# QUTMS-BrakeLight-S00.net
KiCad netlist of a schematic drawn in Altium Designer
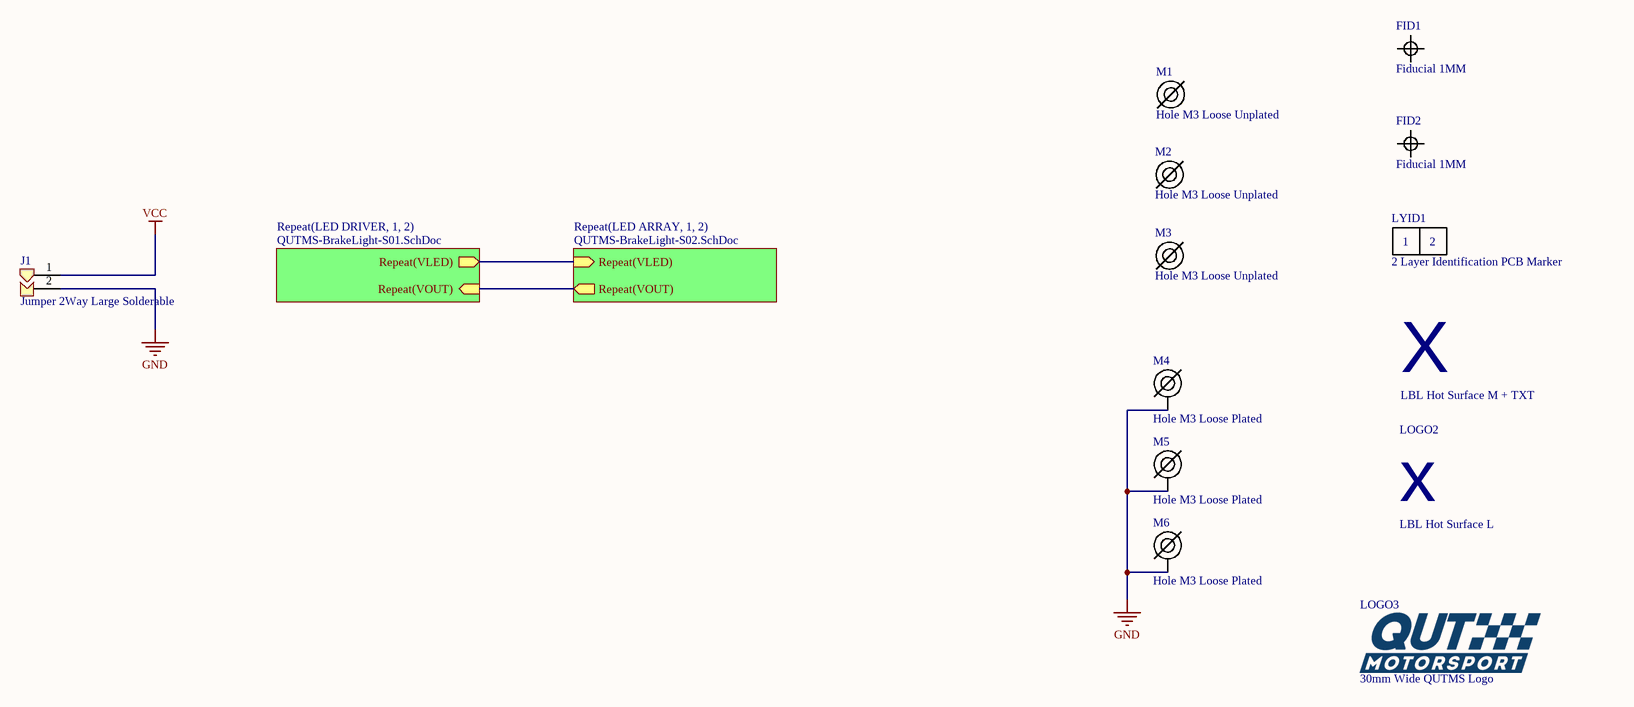
[diagram p0: QUTMS-BrakeLight-S00.SchDoc]

(export (version "E")
  (design (tool "Eeschema 10.0.6"))
  (components
    (comp (ref "FID1")
      (value "Fiducial 1MM")
      (footprint "FIDUCIAL 1MM")
      (libsource (lib "QUTMS_PCBLibrary") (part "Fiducial 1MM"))
    )
    (comp (ref "FID2")
      (value "Fiducial 1MM")
      (footprint "FIDUCIAL 1MM")
      (libsource (lib "QUTMS_PCBLibrary") (part "Fiducial 1MM"))
    )
    (comp (ref "J1")
      (value "Jumper 2Way Large Solderable")
      (footprint "Jumper_2Way_Large_Solder_Pad")
      (description "Jumper 2Way Large Side Solderable Pad")
      (libsource (lib "QUTMS_JumperLibrary") (part "Jumper 2Way Side Large Solder Pad"))
    )
    (comp (ref "LOGO1")
      (value "LBL Hot Surface M + TXT")
      (footprint "LBL HOT MEDIUM TXT")
      (libsource (lib "QUTMS_PCBLibrary") (part "LBL Hot Surface M + TXT"))
    )
    (comp (ref "LOGO2")
      (value "LBL Hot Surface L")
      (footprint "LBL HOT LARGE")
      (libsource (lib "QUTMS_PCBLibrary") (part "LBL Hot Surface L"))
    )
    (comp (ref "LOGO3")
      (value "30mm Wide QUTMS Logo")
      (footprint "QUTMS LOGO 30MM")
      (libsource (lib "QUTMS_PCBLibrary") (part "QUTMS Logo 30mm"))
    )
    (comp (ref "LYID1")
      (value "2 Layer Identification PCB Marker")
      (footprint "LAYER IDENT 2")
      (libsource (lib "QUTMS_PCBLibrary") (part "Layer Identification 2"))
    )
    (comp (ref "M1")
      (value "Hole M3 Loose Unplated")
      (footprint "M3.5 UNPLATED")
      (description "M3.5 Hole, No Plating")
      (libsource (lib "QUTMS_PCBLibrary") (part "Hole M3 Loose Unplated"))
    )
    (comp (ref "M2")
      (value "Hole M3 Loose Unplated")
      (footprint "M3.5 UNPLATED")
      (description "M3.5 Hole, No Plating")
      (libsource (lib "QUTMS_PCBLibrary") (part "Hole M3 Loose Unplated"))
    )
    (comp (ref "M3")
      (value "Hole M3 Loose Unplated")
      (footprint "M3.5 UNPLATED")
      (description "M3.5 Hole, No Plating")
      (libsource (lib "QUTMS_PCBLibrary") (part "Hole M3 Loose Unplated"))
    )
    (comp (ref "M4")
      (value "Hole M3 Loose Plated")
      (footprint "M3.5 PLATED")
      (description "M3.5 Hole, Plated")
      (libsource (lib "QUTMS_PCBLibrary") (part "Hole M3 Loose Plated"))
    )
    (comp (ref "M5")
      (value "Hole M3 Loose Plated")
      (footprint "M3.5 PLATED")
      (description "M3.5 Hole, Plated")
      (libsource (lib "QUTMS_PCBLibrary") (part "Hole M3 Loose Plated"))
    )
    (comp (ref "M6")
      (value "Hole M3 Loose Plated")
      (footprint "M3.5 PLATED")
      (description "M3.5 Hole, Plated")
      (libsource (lib "QUTMS_PCBLibrary") (part "Hole M3 Loose Plated"))
    )
  )
  (nets
    (net (code "3") (name "GND") (class "Default")
      (node (ref "J1") (pin "2") (pinfunction "2_2") (pintype "passive"))
      (node (ref "M4") (pin "1") (pinfunction "1_1") (pintype "passive"))
      (node (ref "M5") (pin "1") (pinfunction "1_1") (pintype "passive"))
      (node (ref "M6") (pin "1") (pinfunction "1_1") (pintype "passive"))
    )
    (net (code "4") (name "VCC") (class "Default")
      (node (ref "J1") (pin "1") (pinfunction "1_1") (pintype "passive"))
    )
  )
)
